# attiny85.net
KiCad netlist of a schematic drawn in EAGLE
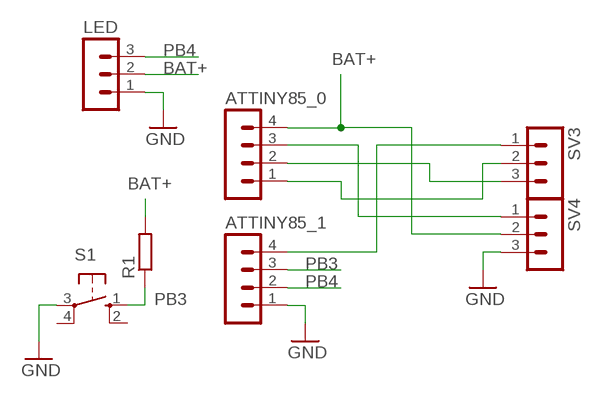
[diagram p0: schematic, sheet 1]

(export (version "E")
  (design (tool "Eeschema 10.0.6"))
  (components
    (comp (ref "ATTINY85_0")
      (value "PINHEAD-MA04-1")
      (footprint "eagle-import:PINHEAD-MA04-1")
      (libsource (lib "eagle-import") (part "PINHEAD-MA04-1"))
    )
    (comp (ref "ATTINY85_1")
      (value "PINHEAD-MA04-1")
      (footprint "eagle-import:PINHEAD-MA04-1")
      (libsource (lib "eagle-import") (part "PINHEAD-MA04-1"))
    )
    (comp (ref "LED")
      (value "PINHEAD-MA03-1")
      (footprint "eagle-import:PINHEAD-MA03-1")
      (libsource (lib "eagle-import") (part "PINHEAD-MA03-1"))
    )
    (comp (ref "R1")
      (value "R-EU_0204/5")
      (footprint "eagle-import:0204_5")
      (libsource (lib "eagle-import") (part "R-EU_0204/5"))
    )
    (comp (ref "S1")
      (value "10-XX")
      (footprint "eagle-import:B3F-10XX")
      (fields (field (name "MPN") "B3F-1000"))
      (libsource (lib "eagle-import") (part "10-XX"))
    )
    (comp (ref "SV3")
      (value "PINHEAD-MA03-1")
      (footprint "eagle-import:PINHEAD-MA03-1")
      (libsource (lib "eagle-import") (part "PINHEAD-MA03-1"))
    )
    (comp (ref "SV4")
      (value "PINHEAD-MA03-1")
      (footprint "eagle-import:PINHEAD-MA03-1")
      (libsource (lib "eagle-import") (part "PINHEAD-MA03-1"))
    )
  )
  (nets
    (net (code "1") (name "/BAT+") (class "Default")
      (node (ref "ATTINY85_0") (pin "4") (pinfunction "4_4") (pintype "passive"))
      (node (ref "LED") (pin "2") (pinfunction "2_2") (pintype "passive"))
      (node (ref "R1") (pin "2") (pinfunction "2_2") (pintype "passive"))
      (node (ref "SV4") (pin "2") (pinfunction "2_2") (pintype "passive"))
    )
    (net (code "2") (name "/PB3") (class "Default")
      (node (ref "ATTINY85_1") (pin "3") (pinfunction "3_3") (pintype "passive"))
      (node (ref "R1") (pin "1") (pinfunction "1_1") (pintype "passive"))
      (node (ref "S1") (pin "1") (pinfunction "S_1") (pintype "passive"))
    )
    (net (code "3") (name "/PB4") (class "Default")
      (node (ref "ATTINY85_1") (pin "2") (pinfunction "2_2") (pintype "passive"))
      (node (ref "LED") (pin "3") (pinfunction "3_3") (pintype "passive"))
    )
    (net (code "4") (name "GND") (class "Default")
      (node (ref "ATTINY85_1") (pin "1") (pinfunction "1_1") (pintype "passive"))
      (node (ref "LED") (pin "1") (pinfunction "1_1") (pintype "passive"))
      (node (ref "S1") (pin "3") (pinfunction "P_3") (pintype "passive"))
      (node (ref "SV4") (pin "3") (pinfunction "3_3") (pintype "passive"))
    )
    (net (code "5") (name "Net-(ATTINY85_0-Pad1)") (class "Default")
      (node (ref "ATTINY85_0") (pin "1") (pinfunction "1_1") (pintype "passive"))
      (node (ref "SV3") (pin "2") (pinfunction "2_2") (pintype "passive"))
    )
    (net (code "6") (name "Net-(ATTINY85_0-Pad2)") (class "Default")
      (node (ref "ATTINY85_0") (pin "2") (pinfunction "2_2") (pintype "passive"))
      (node (ref "SV3") (pin "3") (pinfunction "3_3") (pintype "passive"))
    )
    (net (code "7") (name "Net-(ATTINY85_0-Pad3)") (class "Default")
      (node (ref "ATTINY85_0") (pin "3") (pinfunction "3_3") (pintype "passive"))
      (node (ref "SV4") (pin "1") (pinfunction "1_1") (pintype "passive"))
    )
    (net (code "8") (name "Net-(ATTINY85_1-Pad4)") (class "Default")
      (node (ref "ATTINY85_1") (pin "4") (pinfunction "4_4") (pintype "passive"))
      (node (ref "SV3") (pin "1") (pinfunction "1_1") (pintype "passive"))
    )
    (net (code "9") (name "unconnected-(S1-P1-Pad4)") (class "Default")
      (node (ref "S1") (pin "4") (pinfunction "P1_4") (pintype "passive"))
    )
    (net (code "10") (name "unconnected-(S1-S1-Pad2)") (class "Default")
      (node (ref "S1") (pin "2") (pinfunction "S1_2") (pintype "passive"))
    )
  )
)
